# PSU_Schematic.net
KiCad netlist of a schematic drawn in Altium Designer
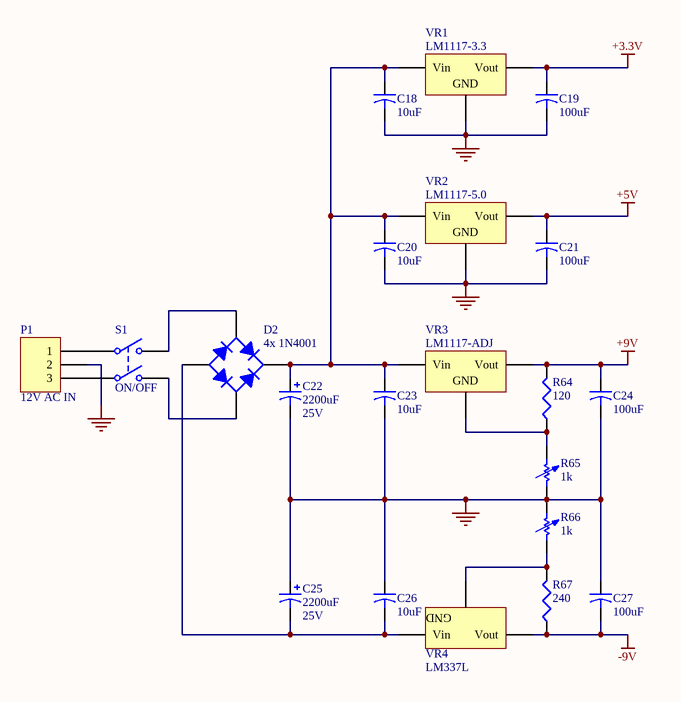
[diagram p0: PSU.Schematic.SchDoc]

(export (version "E")
  (design (tool "Eeschema 10.0.6"))
  (components
    (comp (ref "C18")
      (value "10uF")
      (footprint "CAPR5-4X5")
      (description "Capacitor")
      (fields (field (name "PUBLISHER") "Altium Limited"))
      (libsource (lib "Miscellaneous Devices") (part "Cap2"))
    )
    (comp (ref "C19")
      (value "100uF")
      (footprint "CAPR5-4X5")
      (description "Capacitor")
      (fields (field (name "PUBLISHER") "Altium Limited"))
      (libsource (lib "Miscellaneous Devices") (part "Cap2"))
    )
    (comp (ref "C20")
      (value "10uF")
      (footprint "CAPR5-4X5")
      (description "Capacitor")
      (fields (field (name "PUBLISHER") "Altium Limited"))
      (libsource (lib "Miscellaneous Devices") (part "Cap2"))
    )
    (comp (ref "C21")
      (value "100uF")
      (footprint "CAPR5-4X5")
      (description "Capacitor")
      (fields (field (name "PUBLISHER") "Altium Limited"))
      (libsource (lib "Miscellaneous Devices") (part "Cap2"))
    )
    (comp (ref "C22")
      (value "2200uF")
      (footprint "RB7.6-15")
      (description "Polarized Capacitor (Radial)")
      (fields (field (name "ALTIUM_VALUE") "25V") (field (name "PUBLISHER") "Altium Limited"))
      (libsource (lib "Miscellaneous Devices") (part "Cap Pol1"))
    )
    (comp (ref "C23")
      (value "10uF")
      (footprint "CAPR5-4X5")
      (description "Capacitor")
      (fields (field (name "PUBLISHER") "Altium Limited"))
      (libsource (lib "Miscellaneous Devices") (part "Cap2"))
    )
    (comp (ref "C24")
      (value "100uF")
      (footprint "CAPR5-4X5")
      (description "Capacitor")
      (fields (field (name "PUBLISHER") "Altium Limited"))
      (libsource (lib "Miscellaneous Devices") (part "Cap2"))
    )
    (comp (ref "C25")
      (value "2200uF")
      (footprint "RB7.6-15")
      (description "Polarized Capacitor (Radial)")
      (fields (field (name "ALTIUM_VALUE") "25V") (field (name "PUBLISHER") "Altium Limited"))
      (libsource (lib "Miscellaneous Devices") (part "Cap Pol1"))
    )
    (comp (ref "C26")
      (value "10uF")
      (footprint "CAPR5-4X5")
      (description "Capacitor")
      (fields (field (name "PUBLISHER") "Altium Limited"))
      (libsource (lib "Miscellaneous Devices") (part "Cap2"))
    )
    (comp (ref "C27")
      (value "100uF")
      (footprint "CAPR5-4X5")
      (description "Capacitor")
      (fields (field (name "PUBLISHER") "Altium Limited"))
      (libsource (lib "Miscellaneous Devices") (part "Cap2"))
    )
    (comp (ref "D2")
      (value "4x 1N4001")
      (footprint "D-38")
      (description "Full Wave Diode Bridge")
      (fields (field (name "PUBLISHER") "Altium Limited"))
      (libsource (lib "Miscellaneous Devices") (part "Bridge1"))
    )
    (comp (ref "P1")
      (value "12V AC IN")
      (footprint "HDR1X3")
      (description "Header, 3-Pin")
      (fields (field (name "PUBLISHER") "Altium Limited"))
      (libsource (lib "Miscellaneous Connectors") (part "Header 3"))
    )
    (comp (ref "R64")
      (value "120")
      (footprint "J1-0603")
      (description "Resistor")
      (fields (field (name "PUBLISHER") "Altium Limited"))
      (libsource (lib "Miscellaneous Devices") (part "Res3"))
    )
    (comp (ref "R65")
      (value "1k")
      (footprint "AXIAL-0.7")
      (description "Variable Resistor")
      (fields (field (name "PUBLISHER") "Altium Limited"))
      (libsource (lib "Miscellaneous Devices") (part "Res Adj1"))
    )
    (comp (ref "R66")
      (value "1k")
      (footprint "AXIAL-0.7")
      (description "Variable Resistor")
      (fields (field (name "PUBLISHER") "Altium Limited"))
      (libsource (lib "Miscellaneous Devices") (part "Res Adj1"))
    )
    (comp (ref "R67")
      (value "240")
      (footprint "J1-0603")
      (description "Resistor")
      (fields (field (name "PUBLISHER") "Altium Limited"))
      (libsource (lib "Miscellaneous Devices") (part "Res3"))
    )
    (comp (ref "S1")
      (value "ON/OFF")
      (footprint "DPST-4")
      (description "Double-Pole, Single-Throw Switch")
      (fields (field (name "PUBLISHER") "Altium Limited"))
      (libsource (lib "Miscellaneous Devices") (part "SW-DPST"))
    )
    (comp (ref "VR1")
      (value "LM1117-3.3")
      (footprint "D2PAK_N")
      (description "Voltage Regulator")
      (fields (field (name "PUBLISHER") "Altium Limited"))
      (libsource (lib "") (part "Volt Reg_1"))
    )
    (comp (ref "VR2")
      (value "LM1117-5.0")
      (footprint "D2PAK_N")
      (description "Voltage Regulator")
      (fields (field (name "PUBLISHER") "Altium Limited"))
      (libsource (lib "") (part "Volt Reg_1"))
    )
    (comp (ref "VR3")
      (value "LM1117-ADJ")
      (footprint "D2PAK_N")
      (description "Voltage Regulator")
      (fields (field (name "PUBLISHER") "Altium Limited"))
      (libsource (lib "") (part "Volt Reg_1"))
    )
    (comp (ref "VR4")
      (value "LM337L")
      (footprint "D2PAK_N")
      (description "Voltage Regulator")
      (fields (field (name "PUBLISHER") "Altium Limited"))
      (libsource (lib "Miscellaneous Devices") (part "Volt Reg"))
    )
  )
  (nets
    (net (code "1") (name "+3.3V") (class "Default")
      (node (ref "C19") (pin "1") (pinfunction "1_1") (pintype "passive"))
      (node (ref "VR1") (pin "3") (pinfunction "Vout_3") (pintype "passive"))
    )
    (net (code "2") (name "+5V") (class "Default")
      (node (ref "C21") (pin "1") (pinfunction "1_1") (pintype "passive"))
      (node (ref "VR2") (pin "3") (pinfunction "Vout_3") (pintype "passive"))
    )
    (net (code "3") (name "+9V") (class "Default")
      (node (ref "C24") (pin "1") (pinfunction "1_1") (pintype "passive"))
      (node (ref "R64") (pin "2") (pinfunction "2_2") (pintype "passive"))
      (node (ref "VR3") (pin "3") (pinfunction "Vout_3") (pintype "passive"))
    )
    (net (code "4") (name "-9V") (class "Default")
      (node (ref "C27") (pin "2") (pinfunction "2_2") (pintype "passive"))
      (node (ref "R67") (pin "1") (pinfunction "1_1") (pintype "passive"))
      (node (ref "VR4") (pin "3") (pinfunction "Vout_3") (pintype "passive"))
    )
    (net (code "5") (name "GND") (class "Default")
      (node (ref "C18") (pin "2") (pinfunction "2_2") (pintype "passive"))
      (node (ref "C19") (pin "2") (pinfunction "2_2") (pintype "passive"))
      (node (ref "C20") (pin "2") (pinfunction "2_2") (pintype "passive"))
      (node (ref "C21") (pin "2") (pinfunction "2_2") (pintype "passive"))
      (node (ref "C22") (pin "2") (pinfunction "2_2") (pintype "passive"))
      (node (ref "C23") (pin "2") (pinfunction "2_2") (pintype "passive"))
      (node (ref "C24") (pin "2") (pinfunction "2_2") (pintype "passive"))
      (node (ref "C25") (pin "1") (pinfunction "1_1") (pintype "passive"))
      (node (ref "C26") (pin "1") (pinfunction "1_1") (pintype "passive"))
      (node (ref "C27") (pin "1") (pinfunction "1_1") (pintype "passive"))
      (node (ref "P1") (pin "2") (pinfunction "2_2") (pintype "passive"))
      (node (ref "R65") (pin "1") (pinfunction "1_1") (pintype "passive"))
      (node (ref "R66") (pin "2") (pinfunction "2_2") (pintype "passive"))
      (node (ref "VR1") (pin "2") (pinfunction "GND_2") (pintype "passive"))
      (node (ref "VR2") (pin "2") (pinfunction "GND_2") (pintype "passive"))
    )
    (net (code "6") (name "Net-(D2-A)") (class "Default")
      (node (ref "C25") (pin "2") (pinfunction "2_2") (pintype "passive"))
      (node (ref "C26") (pin "2") (pinfunction "2_2") (pintype "passive"))
      (node (ref "D2") (pin "3") (pinfunction "A_3") (pintype "passive"))
      (node (ref "VR4") (pin "1") (pinfunction "Vin_1") (pintype "passive"))
    )
    (net (code "7") (name "Net-(D2-K)") (class "Default")
      (node (ref "C18") (pin "1") (pinfunction "1_1") (pintype "passive"))
      (node (ref "C20") (pin "1") (pinfunction "1_1") (pintype "passive"))
      (node (ref "C22") (pin "1") (pinfunction "1_1") (pintype "passive"))
      (node (ref "C23") (pin "1") (pinfunction "1_1") (pintype "passive"))
      (node (ref "D2") (pin "1") (pinfunction "K_1") (pintype "passive"))
      (node (ref "VR1") (pin "1") (pinfunction "Vin_1") (pintype "passive"))
      (node (ref "VR2") (pin "1") (pinfunction "Vin_1") (pintype "passive"))
      (node (ref "VR3") (pin "1") (pinfunction "Vin_1") (pintype "passive"))
    )
    (net (code "8") (name "Net-(S1-COMMON1)") (class "Default")
      (node (ref "P1") (pin "1") (pinfunction "1_1") (pintype "passive"))
      (node (ref "S1") (pin "1") (pinfunction "COMMON1_1") (pintype "passive"))
    )
    (net (code "9") (name "Net-(S1-COMMON2)") (class "Default")
      (node (ref "P1") (pin "3") (pinfunction "3_3") (pintype "passive"))
      (node (ref "S1") (pin "3") (pinfunction "COMMON2_3") (pintype "passive"))
    )
    (net (code "10") (name "Net-(S1-NO1)") (class "Default")
      (node (ref "D2") (pin "4") (pinfunction "C_4") (pintype "passive"))
      (node (ref "S1") (pin "2") (pinfunction "NO1_2") (pintype "passive"))
    )
    (net (code "11") (name "Net-(S1-NO2)") (class "Default")
      (node (ref "D2") (pin "2") (pinfunction "C_2") (pintype "passive"))
      (node (ref "S1") (pin "4") (pinfunction "NO2_4") (pintype "passive"))
    )
    (net (code "12") (name "Net-(VR3-GND)") (class "Default")
      (node (ref "R64") (pin "1") (pinfunction "1_1") (pintype "passive"))
      (node (ref "R65") (pin "2") (pinfunction "2_2") (pintype "passive"))
      (node (ref "VR3") (pin "2") (pinfunction "GND_2") (pintype "passive"))
    )
    (net (code "13") (name "Net-(VR4-ADJ)") (class "Default")
      (node (ref "R66") (pin "1") (pinfunction "1_1") (pintype "passive"))
      (node (ref "R67") (pin "2") (pinfunction "2_2") (pintype "passive"))
      (node (ref "VR4") (pin "2") (pinfunction "ADJ_2") (pintype "passive"))
    )
  )
)
